# Motherboard.net
KiCad netlist of a schematic drawn in EAGLE
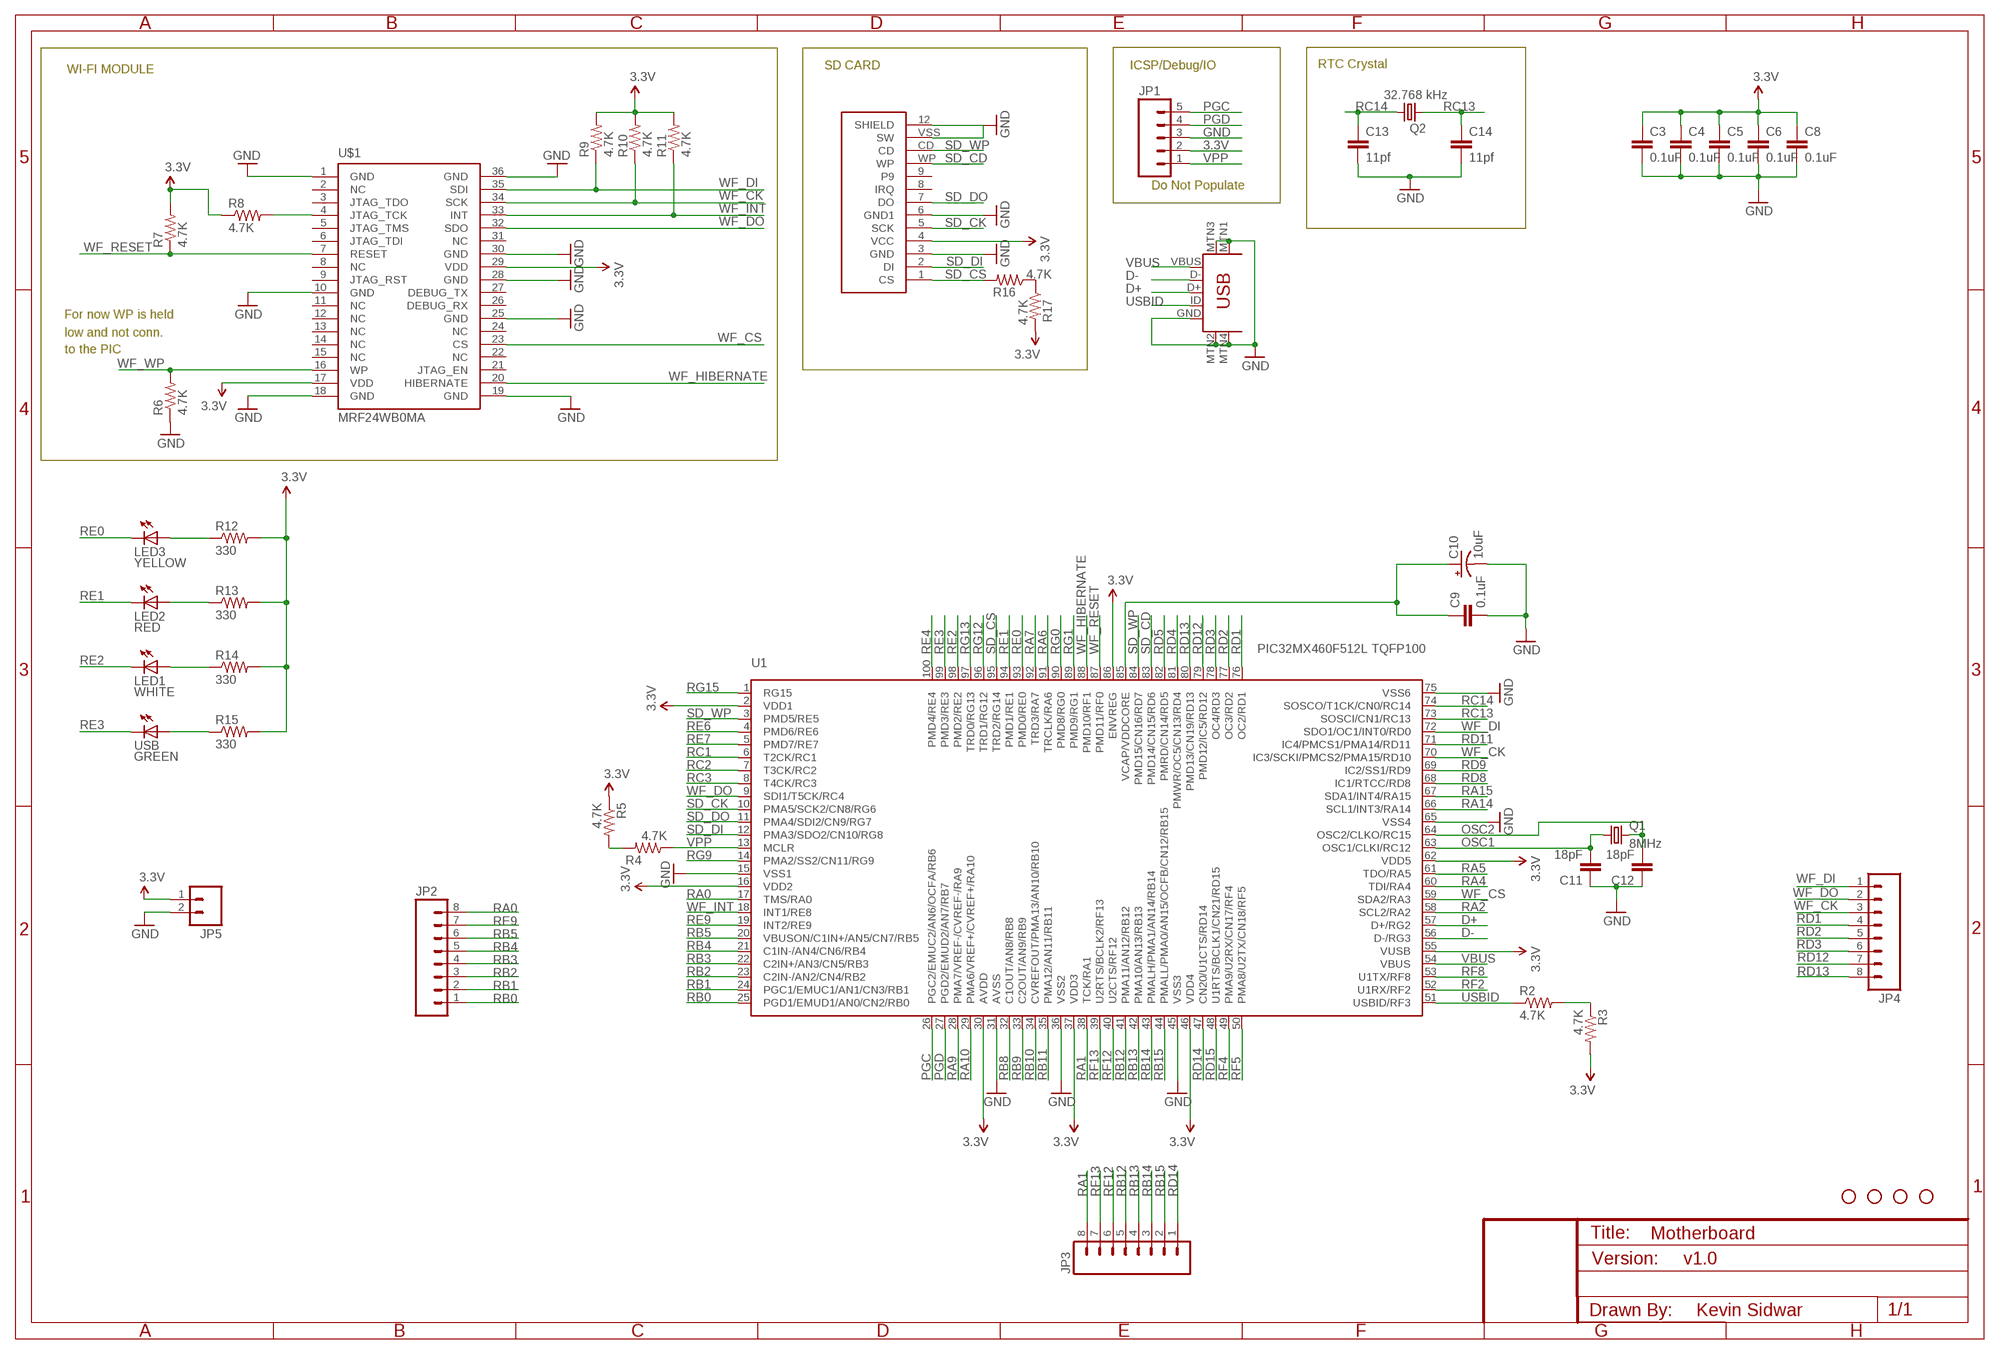
[diagram p0: schematic, sheet 1]

(export (version "E")
  (design (tool "Eeschema 10.0.6"))
  (components
    (comp (ref "C3")
      (value "0.1uF")
      (footprint "eagle-import:0603")
      (libsource (lib "eagle-import") (part "CAP0603"))
    )
    (comp (ref "C4")
      (value "0.1uF")
      (footprint "eagle-import:0603")
      (libsource (lib "eagle-import") (part "CAP0603"))
    )
    (comp (ref "C5")
      (value "0.1uF")
      (footprint "eagle-import:0603")
      (libsource (lib "eagle-import") (part "CAP0603"))
    )
    (comp (ref "C6")
      (value "0.1uF")
      (footprint "eagle-import:0603")
      (libsource (lib "eagle-import") (part "CAP0603"))
    )
    (comp (ref "C8")
      (value "0.1uF")
      (footprint "eagle-import:0603")
      (libsource (lib "eagle-import") (part "CAP0603"))
    )
    (comp (ref "C9")
      (value "0.1uF")
      (footprint "eagle-import:0603")
      (libsource (lib "eagle-import") (part "CAP0603"))
    )
    (comp (ref "C10")
      (value "10uF")
      (footprint "eagle-import:EIA3528")
      (libsource (lib "eagle-import") (part "CAP_POL3528"))
    )
    (comp (ref "C11")
      (value "18pF")
      (footprint "eagle-import:0603")
      (libsource (lib "eagle-import") (part "CAP0603"))
    )
    (comp (ref "C12")
      (value "18pF")
      (footprint "eagle-import:0603")
      (libsource (lib "eagle-import") (part "CAP0603"))
    )
    (comp (ref "C13")
      (value "11pf")
      (footprint "eagle-import:0603")
      (libsource (lib "eagle-import") (part "CAP0603"))
    )
    (comp (ref "C14")
      (value "11pf")
      (footprint "eagle-import:0603")
      (libsource (lib "eagle-import") (part "CAP0603"))
    )
    (comp (ref "JP1")
      (value "M05LOCK")
      (footprint "eagle-import:1X05_LOCK")
      (libsource (lib "eagle-import") (part "M05LOCK"))
    )
    (comp (ref "JP2")
      (value "M08LOCK")
      (footprint "eagle-import:1X08_LOCK")
      (libsource (lib "eagle-import") (part "M08LOCK"))
    )
    (comp (ref "JP3")
      (value "M08LOCK")
      (footprint "eagle-import:1X08_LOCK")
      (libsource (lib "eagle-import") (part "M08LOCK"))
    )
    (comp (ref "JP4")
      (value "M08LOCK")
      (footprint "eagle-import:1X08_LOCK")
      (libsource (lib "eagle-import") (part "M08LOCK"))
    )
    (comp (ref "JP5")
      (value "M02LOCK")
      (footprint "eagle-import:1X02_LOCK")
      (libsource (lib "eagle-import") (part "M02LOCK"))
    )
    (comp (ref "JP6")
      (value "STAND-OFF")
      (footprint "eagle-import:STAND-OFF")
      (libsource (lib "eagle-import") (part "STAND-OFF"))
    )
    (comp (ref "JP7")
      (value "STAND-OFF")
      (footprint "eagle-import:STAND-OFF")
      (libsource (lib "eagle-import") (part "STAND-OFF"))
    )
    (comp (ref "JP8")
      (value "STAND-OFF")
      (footprint "eagle-import:STAND-OFF")
      (libsource (lib "eagle-import") (part "STAND-OFF"))
    )
    (comp (ref "JP9")
      (value "STAND-OFF")
      (footprint "eagle-import:STAND-OFF")
      (libsource (lib "eagle-import") (part "STAND-OFF"))
    )
    (comp (ref "LED1")
      (value "WHITE")
      (footprint "eagle-import:LED-0603")
      (libsource (lib "eagle-import") (part "LED0603"))
    )
    (comp (ref "LED2")
      (value "RED")
      (footprint "eagle-import:LED-0603")
      (libsource (lib "eagle-import") (part "LED0603"))
    )
    (comp (ref "LED3")
      (value "YELLOW")
      (footprint "eagle-import:LED-0603")
      (libsource (lib "eagle-import") (part "LED0603"))
    )
    (comp (ref "Q1")
      (value "8MHz")
      (footprint "eagle-import:CRYSTAL-SMD-5X3")
      (libsource (lib "eagle-import") (part "CRYSTAL5X3"))
    )
    (comp (ref "Q2")
      (value "32.768 kHz")
      (footprint "eagle-import:CRYSTAL-SMD-4X2")
      (libsource (lib "eagle-import") (part "CRYSTAL"))
    )
    (comp (ref "R2")
      (value "4.7K")
      (footprint "eagle-import:0603-RES")
      (libsource (lib "eagle-import") (part "RESISTOR0603-RES"))
    )
    (comp (ref "R3")
      (value "4.7K")
      (footprint "eagle-import:0603-RES")
      (libsource (lib "eagle-import") (part "RESISTOR0603-RES"))
    )
    (comp (ref "R4")
      (value "4.7K")
      (footprint "eagle-import:0603-RES")
      (libsource (lib "eagle-import") (part "RESISTOR0603-RES"))
    )
    (comp (ref "R5")
      (value "4.7K")
      (footprint "eagle-import:0603-RES")
      (libsource (lib "eagle-import") (part "RESISTOR0603-RES"))
    )
    (comp (ref "R6")
      (value "4.7K")
      (footprint "eagle-import:0603-RES")
      (libsource (lib "eagle-import") (part "RESISTOR0603-RES"))
    )
    (comp (ref "R7")
      (value "4.7K")
      (footprint "eagle-import:0603-RES")
      (libsource (lib "eagle-import") (part "RESISTOR0603-RES"))
    )
    (comp (ref "R8")
      (value "4.7K")
      (footprint "eagle-import:0603-RES")
      (libsource (lib "eagle-import") (part "RESISTOR0603-RES"))
    )
    (comp (ref "R9")
      (value "4.7K")
      (footprint "eagle-import:0603-RES")
      (libsource (lib "eagle-import") (part "RESISTOR0603-RES"))
    )
    (comp (ref "R10")
      (value "4.7K")
      (footprint "eagle-import:0603-RES")
      (libsource (lib "eagle-import") (part "RESISTOR0603-RES"))
    )
    (comp (ref "R11")
      (value "4.7K")
      (footprint "eagle-import:0603-RES")
      (libsource (lib "eagle-import") (part "RESISTOR0603-RES"))
    )
    (comp (ref "R12")
      (value "330")
      (footprint "eagle-import:0603-RES")
      (libsource (lib "eagle-import") (part "RESISTOR0603-RES"))
    )
    (comp (ref "R13")
      (value "330")
      (footprint "eagle-import:0603-RES")
      (libsource (lib "eagle-import") (part "RESISTOR0603-RES"))
    )
    (comp (ref "R14")
      (value "330")
      (footprint "eagle-import:0603-RES")
      (libsource (lib "eagle-import") (part "RESISTOR0603-RES"))
    )
    (comp (ref "R15")
      (value "330")
      (footprint "eagle-import:0603-RES")
      (libsource (lib "eagle-import") (part "RESISTOR0603-RES"))
    )
    (comp (ref "R16")
      (value "4.7K")
      (footprint "eagle-import:0603-RES")
      (libsource (lib "eagle-import") (part "RESISTOR0603-RES"))
    )
    (comp (ref "R17")
      (value "4.7K")
      (footprint "eagle-import:0603-RES")
      (libsource (lib "eagle-import") (part "RESISTOR0603-RES"))
    )
    (comp (ref "U$1")
      (value "MRF24WB0MA")
      (footprint "eagle-import:SMD_MRF")
      (libsource (lib "eagle-import") (part "MRF24WB0MA"))
    )
    (comp (ref "U$2")
      (value "SD_CARD_SOCKETALPS")
      (footprint "eagle-import:SD_ALPS")
      (libsource (lib "eagle-import") (part "SD_CARD_SOCKETALPS"))
    )
    (comp (ref "U$21")
      (value "USB-MINIB-5PIN")
      (footprint "eagle-import:USB-MINIB")
      (libsource (lib "eagle-import") (part "USB-MINIB-5PIN"))
    )
    (comp (ref "U1")
      (value "PIC32MX460F512L TQFP100")
      (footprint "eagle-import:TQFP100")
      (libsource (lib "eagle-import") (part "PIC32MX4XXLTQFP100"))
    )
    (comp (ref "USB")
      (value "GREEN")
      (footprint "eagle-import:LED-0603")
      (libsource (lib "eagle-import") (part "LED0603"))
    )
  )
  (nets
    (net (code "1") (name "/D+") (class "Default")
      (node (ref "U$21") (pin "D+") (pinfunction "D+_D+") (pintype "bidirectional"))
      (node (ref "U1") (pin "57") (pinfunction "D+/RG2_57") (pintype "bidirectional"))
    )
    (net (code "2") (name "/D-") (class "Default")
      (node (ref "U$21") (pin "D-") (pinfunction "D-_D-") (pintype "bidirectional"))
      (node (ref "U1") (pin "56") (pinfunction "D-/RG3_56") (pintype "bidirectional"))
    )
    (net (code "3") (name "/OSC1") (class "Default")
      (node (ref "C11") (pin "2") (pinfunction "2_2") (pintype "passive"))
      (node (ref "Q1") (pin "1") (pinfunction "1_1") (pintype "passive"))
      (node (ref "U1") (pin "63") (pinfunction "OSC1/CLKI/RC12_63") (pintype "bidirectional"))
    )
    (net (code "4") (name "/OSC2") (class "Default")
      (node (ref "C12") (pin "2") (pinfunction "2_2") (pintype "passive"))
      (node (ref "Q1") (pin "3") (pinfunction "2_3") (pintype "passive"))
      (node (ref "U1") (pin "64") (pinfunction "OSC2/CLKO/RC15_64") (pintype "bidirectional"))
    )
    (net (code "5") (name "/PGC") (class "Default")
      (node (ref "JP1") (pin "5") (pinfunction "5_5") (pintype "passive"))
      (node (ref "U1") (pin "26") (pinfunction "PGC2/EMUC2/AN6/OCFA/RB6_26") (pintype "bidirectional"))
    )
    (net (code "6") (name "/PGD") (class "Default")
      (node (ref "JP1") (pin "4") (pinfunction "4_4") (pintype "passive"))
      (node (ref "U1") (pin "27") (pinfunction "PGD2/EMUD2/AN7/RB7_27") (pintype "bidirectional"))
    )
    (net (code "7") (name "/RA0") (class "Default")
      (node (ref "JP2") (pin "8") (pinfunction "8_8") (pintype "passive"))
      (node (ref "U1") (pin "17") (pinfunction "TMS/RA0_17") (pintype "bidirectional"))
    )
    (net (code "8") (name "/RA1") (class "Default")
      (node (ref "JP3") (pin "8") (pinfunction "8_8") (pintype "passive"))
      (node (ref "U1") (pin "38") (pinfunction "TCK/RA1_38") (pintype "bidirectional"))
    )
    (net (code "9") (name "/RA2") (class "Default")
      (node (ref "U1") (pin "58") (pinfunction "SCL2/RA2_58") (pintype "bidirectional"))
    )
    (net (code "10") (name "/RA4") (class "Default")
      (node (ref "U1") (pin "60") (pinfunction "TDI/RA4_60") (pintype "bidirectional"))
    )
    (net (code "11") (name "/RA5") (class "Default")
      (node (ref "U1") (pin "61") (pinfunction "TDO/RA5_61") (pintype "bidirectional"))
    )
    (net (code "12") (name "/RA6") (class "Default")
      (node (ref "U1") (pin "91") (pinfunction "TRCLK/RA6_91") (pintype "bidirectional"))
    )
    (net (code "13") (name "/RA7") (class "Default")
      (node (ref "U1") (pin "92") (pinfunction "TRD3/RA7_92") (pintype "bidirectional"))
    )
    (net (code "14") (name "/RA9") (class "Default")
      (node (ref "U1") (pin "28") (pinfunction "PMA7/VREF-/CVREF-/RA9_28") (pintype "bidirectional"))
    )
    (net (code "15") (name "/RA10") (class "Default")
      (node (ref "U1") (pin "29") (pinfunction "PMA6/VREF+/CVREF+/RA10_29") (pintype "bidirectional"))
    )
    (net (code "16") (name "/RA14") (class "Default")
      (node (ref "U1") (pin "66") (pinfunction "SCL1/INT3/RA14_66") (pintype "bidirectional"))
    )
    (net (code "17") (name "/RA15") (class "Default")
      (node (ref "U1") (pin "67") (pinfunction "SDA1/INT4/RA15_67") (pintype "bidirectional"))
    )
    (net (code "18") (name "/RB0") (class "Default")
      (node (ref "JP2") (pin "1") (pinfunction "1_1") (pintype "passive"))
      (node (ref "U1") (pin "25") (pinfunction "PGD1/EMUD1/AN0/CN2/RB0_25") (pintype "bidirectional"))
    )
    (net (code "19") (name "/RB1") (class "Default")
      (node (ref "JP2") (pin "2") (pinfunction "2_2") (pintype "passive"))
      (node (ref "U1") (pin "24") (pinfunction "PGC1/EMUC1/AN1/CN3/RB1_24") (pintype "bidirectional"))
    )
    (net (code "20") (name "/RB2") (class "Default")
      (node (ref "JP2") (pin "3") (pinfunction "3_3") (pintype "passive"))
      (node (ref "U1") (pin "23") (pinfunction "C2IN-/AN2/CN4/RB2_23") (pintype "bidirectional"))
    )
    (net (code "21") (name "/RB3") (class "Default")
      (node (ref "JP2") (pin "4") (pinfunction "4_4") (pintype "passive"))
      (node (ref "U1") (pin "22") (pinfunction "C2IN+/AN3/CN5/RB3_22") (pintype "bidirectional"))
    )
    (net (code "22") (name "/RB4") (class "Default")
      (node (ref "JP2") (pin "5") (pinfunction "5_5") (pintype "passive"))
      (node (ref "U1") (pin "21") (pinfunction "C1IN-/AN4/CN6/RB4_21") (pintype "bidirectional"))
    )
    (net (code "23") (name "/RB5") (class "Default")
      (node (ref "JP2") (pin "6") (pinfunction "6_6") (pintype "passive"))
      (node (ref "U1") (pin "20") (pinfunction "VBUSON/C1IN+/AN5/CN7/RB5_20") (pintype "bidirectional"))
    )
    (net (code "24") (name "/RB8") (class "Default")
      (node (ref "U1") (pin "32") (pinfunction "C1OUT/AN8/RB8_32") (pintype "bidirectional"))
    )
    (net (code "25") (name "/RB9") (class "Default")
      (node (ref "U1") (pin "33") (pinfunction "C2OUT/AN9/RB9_33") (pintype "bidirectional"))
    )
    (net (code "26") (name "/RB10") (class "Default")
      (node (ref "U1") (pin "34") (pinfunction "CVREFOUT/PMA13/AN10/RB10_34") (pintype "bidirectional"))
    )
    (net (code "27") (name "/RB11") (class "Default")
      (node (ref "U1") (pin "35") (pinfunction "PMA12/AN11/RB11_35") (pintype "bidirectional"))
    )
    (net (code "28") (name "/RB12") (class "Default")
      (node (ref "JP3") (pin "5") (pinfunction "5_5") (pintype "passive"))
      (node (ref "U1") (pin "41") (pinfunction "PMA11/AN12/RB12_41") (pintype "bidirectional"))
    )
    (net (code "29") (name "/RB13") (class "Default")
      (node (ref "JP3") (pin "4") (pinfunction "4_4") (pintype "passive"))
      (node (ref "U1") (pin "42") (pinfunction "PMA10/AN13/RB13_42") (pintype "bidirectional"))
    )
    (net (code "30") (name "/RB14") (class "Default")
      (node (ref "JP3") (pin "3") (pinfunction "3_3") (pintype "passive"))
      (node (ref "U1") (pin "43") (pinfunction "PMALH/PMA1/AN14/RB14_43") (pintype "bidirectional"))
    )
    (net (code "31") (name "/RB15") (class "Default")
      (node (ref "JP3") (pin "2") (pinfunction "2_2") (pintype "passive"))
      (node (ref "U1") (pin "44") (pinfunction "PMALL/PMA0/AN15/OCFB/CN12/RB15_44") (pintype "bidirectional"))
    )
    (net (code "32") (name "/RC1") (class "Default")
      (node (ref "U1") (pin "6") (pinfunction "T2CK/RC1_6") (pintype "bidirectional"))
    )
    (net (code "33") (name "/RC2") (class "Default")
      (node (ref "U1") (pin "7") (pinfunction "T3CK/RC2_7") (pintype "bidirectional"))
    )
    (net (code "34") (name "/RC3") (class "Default")
      (node (ref "U1") (pin "8") (pinfunction "T4CK/RC3_8") (pintype "bidirectional"))
    )
    (net (code "35") (name "/RC13") (class "Default")
      (node (ref "C14") (pin "1") (pinfunction "1_1") (pintype "passive"))
      (node (ref "Q2") (pin "P$2") (pinfunction "2_P$2") (pintype "passive"))
      (node (ref "U1") (pin "73") (pinfunction "SOSCI/CN1/RC13_73") (pintype "bidirectional"))
    )
    (net (code "36") (name "/RC14") (class "Default")
      (node (ref "C13") (pin "1") (pinfunction "1_1") (pintype "passive"))
      (node (ref "Q2") (pin "P$1") (pinfunction "1_P$1") (pintype "passive"))
      (node (ref "U1") (pin "74") (pinfunction "SOSCO/T1CK/CN0/RC14_74") (pintype "bidirectional"))
    )
    (net (code "37") (name "/RD1") (class "Default")
      (node (ref "JP4") (pin "4") (pinfunction "4_4") (pintype "passive"))
      (node (ref "U1") (pin "76") (pinfunction "OC2/RD1_76") (pintype "bidirectional"))
    )
    (net (code "38") (name "/RD2") (class "Default")
      (node (ref "JP4") (pin "5") (pinfunction "5_5") (pintype "passive"))
      (node (ref "U1") (pin "77") (pinfunction "OC3/RD2_77") (pintype "bidirectional"))
    )
    (net (code "39") (name "/RD3") (class "Default")
      (node (ref "JP4") (pin "6") (pinfunction "6_6") (pintype "passive"))
      (node (ref "U1") (pin "78") (pinfunction "OC4/RD3_78") (pintype "bidirectional"))
    )
    (net (code "40") (name "/RD4") (class "Default")
      (node (ref "U1") (pin "81") (pinfunction "PMWR/OC5/CN13/RD4_81") (pintype "bidirectional"))
    )
    (net (code "41") (name "/RD5") (class "Default")
      (node (ref "U1") (pin "82") (pinfunction "PMRD/CN14/RD5_82") (pintype "bidirectional"))
    )
    (net (code "42") (name "/RD8") (class "Default")
      (node (ref "U1") (pin "68") (pinfunction "IC1/RTCC/RD8_68") (pintype "bidirectional"))
    )
    (net (code "43") (name "/RD9") (class "Default")
      (node (ref "U1") (pin "69") (pinfunction "IC2/SS1/RD9_69") (pintype "bidirectional"))
    )
    (net (code "44") (name "/RD11") (class "Default")
      (node (ref "U1") (pin "71") (pinfunction "IC4/PMCS1/PMA14/RD11_71") (pintype "bidirectional"))
    )
    (net (code "45") (name "/RD12") (class "Default")
      (node (ref "JP4") (pin "7") (pinfunction "7_7") (pintype "passive"))
      (node (ref "U1") (pin "79") (pinfunction "PMD12/IC5/RD12_79") (pintype "bidirectional"))
    )
    (net (code "46") (name "/RD13") (class "Default")
      (node (ref "JP4") (pin "8") (pinfunction "8_8") (pintype "passive"))
      (node (ref "U1") (pin "80") (pinfunction "PMD13/CN19/RD13_80") (pintype "bidirectional"))
    )
    (net (code "47") (name "/RD14") (class "Default")
      (node (ref "JP3") (pin "1") (pinfunction "1_1") (pintype "passive"))
      (node (ref "U1") (pin "47") (pinfunction "CN20/U1CTS/RD14_47") (pintype "bidirectional"))
    )
    (net (code "48") (name "/RD15") (class "Default")
      (node (ref "U1") (pin "48") (pinfunction "U1RTS/BCLK1/CN21/RD15_48") (pintype "bidirectional"))
    )
    (net (code "49") (name "/RE0") (class "Default")
      (node (ref "LED3") (pin "C") (pinfunction "C_C") (pintype "passive"))
      (node (ref "U1") (pin "93") (pinfunction "PMD0/RE0_93") (pintype "bidirectional"))
    )
    (net (code "50") (name "/RE1") (class "Default")
      (node (ref "LED2") (pin "C") (pinfunction "C_C") (pintype "passive"))
      (node (ref "U1") (pin "94") (pinfunction "PMD1/RE1_94") (pintype "bidirectional"))
    )
    (net (code "51") (name "/RE2") (class "Default")
      (node (ref "LED1") (pin "C") (pinfunction "C_C") (pintype "passive"))
      (node (ref "U1") (pin "98") (pinfunction "PMD2/RE2_98") (pintype "bidirectional"))
    )
    (net (code "52") (name "/RE3") (class "Default")
      (node (ref "U1") (pin "99") (pinfunction "PMD3/RE3_99") (pintype "bidirectional"))
      (node (ref "USB") (pin "C") (pinfunction "C_C") (pintype "passive"))
    )
    (net (code "53") (name "/RE4") (class "Default")
      (node (ref "U1") (pin "100") (pinfunction "PMD4/RE4_100") (pintype "bidirectional"))
    )
    (net (code "54") (name "/RE6") (class "Default")
      (node (ref "U1") (pin "4") (pinfunction "PMD6/RE6_4") (pintype "bidirectional"))
    )
    (net (code "55") (name "/RE7") (class "Default")
      (node (ref "U1") (pin "5") (pinfunction "PMD7/RE7_5") (pintype "bidirectional"))
    )
    (net (code "56") (name "/RE9") (class "Default")
      (node (ref "JP2") (pin "7") (pinfunction "7_7") (pintype "passive"))
      (node (ref "U1") (pin "19") (pinfunction "INT2/RE9_19") (pintype "bidirectional"))
    )
    (net (code "57") (name "/RF2") (class "Default")
      (node (ref "U1") (pin "52") (pinfunction "U1RX/RF2_52") (pintype "bidirectional"))
    )
    (net (code "58") (name "/RF4") (class "Default")
      (node (ref "U1") (pin "49") (pinfunction "PMA9/U2RX/CN17/RF4_49") (pintype "bidirectional"))
    )
    (net (code "59") (name "/RF5") (class "Default")
      (node (ref "U1") (pin "50") (pinfunction "PMA8/U2TX/CN18/RF5_50") (pintype "bidirectional"))
    )
    (net (code "60") (name "/RF8") (class "Default")
      (node (ref "U1") (pin "53") (pinfunction "U1TX/RF8_53") (pintype "bidirectional"))
    )
    (net (code "61") (name "/RF12") (class "Default")
      (node (ref "JP3") (pin "6") (pinfunction "6_6") (pintype "passive"))
      (node (ref "U1") (pin "40") (pinfunction "U2CTS/RF12_40") (pintype "bidirectional"))
    )
    (net (code "62") (name "/RF13") (class "Default")
      (node (ref "JP3") (pin "7") (pinfunction "7_7") (pintype "passive"))
      (node (ref "U1") (pin "39") (pinfunction "U2RTS/BCLK2/RF13_39") (pintype "bidirectional"))
    )
    (net (code "63") (name "/RG0") (class "Default")
      (node (ref "U1") (pin "90") (pinfunction "PMD8/RG0_90") (pintype "bidirectional"))
    )
    (net (code "64") (name "/RG1") (class "Default")
      (node (ref "U1") (pin "89") (pinfunction "PMD9/RG1_89") (pintype "bidirectional"))
    )
    (net (code "65") (name "/RG9") (class "Default")
      (node (ref "U1") (pin "14") (pinfunction "PMA2/SS2/CN11/RG9_14") (pintype "bidirectional"))
    )
    (net (code "66") (name "/RG12") (class "Default")
      (node (ref "U1") (pin "96") (pinfunction "TRD1/RG12_96") (pintype "bidirectional"))
    )
    (net (code "67") (name "/RG13") (class "Default")
      (node (ref "U1") (pin "97") (pinfunction "TRD0/RG13_97") (pintype "bidirectional"))
    )
    (net (code "68") (name "/RG15") (class "Default")
      (node (ref "U1") (pin "1") (pinfunction "RG15_1") (pintype "bidirectional"))
    )
    (net (code "69") (name "/SD_CD") (class "Default")
      (node (ref "U$2") (pin "WP") (pinfunction "WP_WP") (pintype "bidirectional"))
      (node (ref "U1") (pin "83") (pinfunction "PMD14/CN15/RD6_83") (pintype "bidirectional"))
    )
    (net (code "70") (name "/SD_CK") (class "Default")
      (node (ref "U$2") (pin "5") (pinfunction "SCK_5") (pintype "bidirectional"))
      (node (ref "U1") (pin "10") (pinfunction "PMA5/SCK2/CN8/RG6_10") (pintype "bidirectional"))
    )
    (net (code "71") (name "/SD_CS") (class "Default")
      (node (ref "R16") (pin "2") (pinfunction "2_2") (pintype "passive"))
      (node (ref "U$2") (pin "1") (pinfunction "CS_1") (pintype "bidirectional"))
      (node (ref "U1") (pin "95") (pinfunction "TRD2/RG14_95") (pintype "bidirectional"))
    )
    (net (code "72") (name "/SD_DI") (class "Default")
      (node (ref "U$2") (pin "2") (pinfunction "DI_2") (pintype "bidirectional"))
      (node (ref "U1") (pin "12") (pinfunction "PMA3/SDO2/CN10/RG8_12") (pintype "bidirectional"))
    )
    (net (code "73") (name "/SD_DO") (class "Default")
      (node (ref "U$2") (pin "7") (pinfunction "DO_7") (pintype "bidirectional"))
      (node (ref "U1") (pin "11") (pinfunction "PMA4/SDI2/CN9/RG7_11") (pintype "bidirectional"))
    )
    (net (code "74") (name "/SD_WP") (class "Default")
      (node (ref "U$2") (pin "CD") (pinfunction "CD_CD") (pintype "bidirectional"))
      (node (ref "U1") (pin "3") (pinfunction "PMD5/RE5_3") (pintype "bidirectional"))
      (node (ref "U1") (pin "84") (pinfunction "PMD15/CN16/RD7_84") (pintype "bidirectional"))
    )
    (net (code "75") (name "/USBID") (class "Default")
      (node (ref "R2") (pin "1") (pinfunction "1_1") (pintype "passive"))
      (node (ref "U$21") (pin "ID") (pinfunction "ID_ID") (pintype "bidirectional"))
      (node (ref "U1") (pin "51") (pinfunction "USBID/RF3_51") (pintype "bidirectional"))
    )
    (net (code "76") (name "/VBUS") (class "Default")
      (node (ref "U$21") (pin "VBUS") (pinfunction "VBUS_VBUS") (pintype "bidirectional"))
      (node (ref "U1") (pin "54") (pinfunction "VBUS_54") (pintype "bidirectional"))
    )
    (net (code "77") (name "/VPP") (class "Default")
      (node (ref "JP1") (pin "1") (pinfunction "1_1") (pintype "passive"))
      (node (ref "R4") (pin "1") (pinfunction "1_1") (pintype "passive"))
      (node (ref "U1") (pin "13") (pinfunction "MCLR_13") (pintype "bidirectional"))
    )
    (net (code "78") (name "/WF_CK") (class "Default")
      (node (ref "JP4") (pin "3") (pinfunction "3_3") (pintype "passive"))
      (node (ref "R10") (pin "1") (pinfunction "1_1") (pintype "passive"))
      (node (ref "U$1") (pin "34") (pinfunction "SCK_34") (pintype "bidirectional"))
      (node (ref "U1") (pin "70") (pinfunction "IC3/SCKI/PMCS2/PMA15/RD10_70") (pintype "bidirectional"))
    )
    (net (code "79") (name "/WF_CS") (class "Default")
      (node (ref "U$1") (pin "23") (pinfunction "CS_23") (pintype "bidirectional"))
      (node (ref "U1") (pin "59") (pinfunction "SDA2/RA3_59") (pintype "bidirectional"))
    )
    (net (code "80") (name "/WF_DI") (class "Default")
      (node (ref "JP4") (pin "1") (pinfunction "1_1") (pintype "passive"))
      (node (ref "R9") (pin "1") (pinfunction "1_1") (pintype "passive"))
      (node (ref "U$1") (pin "35") (pinfunction "SDI_35") (pintype "bidirectional"))
      (node (ref "U1") (pin "72") (pinfunction "SDO1/OC1/INT0/RD0_72") (pintype "bidirectional"))
    )
    (net (code "81") (name "/WF_DO") (class "Default")
      (node (ref "JP4") (pin "2") (pinfunction "2_2") (pintype "passive"))
      (node (ref "U$1") (pin "32") (pinfunction "SDO_32") (pintype "bidirectional"))
      (node (ref "U1") (pin "9") (pinfunction "SDI1/T5CK/RC4_9") (pintype "bidirectional"))
    )
    (net (code "82") (name "/WF_HIBERNATE") (class "Default")
      (node (ref "U$1") (pin "20") (pinfunction "HIBERNATE_20") (pintype "bidirectional"))
      (node (ref "U1") (pin "88") (pinfunction "PMD10/RF1_88") (pintype "bidirectional"))
    )
    (net (code "83") (name "/WF_INT") (class "Default")
      (node (ref "R11") (pin "1") (pinfunction "1_1") (pintype "passive"))
      (node (ref "U$1") (pin "33") (pinfunction "INT_33") (pintype "bidirectional"))
      (node (ref "U1") (pin "18") (pinfunction "INT1/RE8_18") (pintype "bidirectional"))
    )
    (net (code "84") (name "/WF_RESET") (class "Default")
      (node (ref "R7") (pin "1") (pinfunction "1_1") (pintype "passive"))
      (node (ref "U$1") (pin "7") (pinfunction "RESET_7") (pintype "bidirectional"))
      (node (ref "U1") (pin "87") (pinfunction "PMD11/RF0_87") (pintype "bidirectional"))
    )
    (net (code "85") (name "/WF_WP") (class "Default")
      (node (ref "R6") (pin "2") (pinfunction "2_2") (pintype "passive"))
      (node (ref "U$1") (pin "16") (pinfunction "WP_16") (pintype "bidirectional"))
    )
    (net (code "86") (name "3.3V") (class "Default")
      (node (ref "C3") (pin "1") (pinfunction "1_1") (pintype "passive"))
      (node (ref "C4") (pin "1") (pinfunction "1_1") (pintype "passive"))
      (node (ref "C5") (pin "1") (pinfunction "1_1") (pintype "passive"))
      (node (ref "C6") (pin "1") (pinfunction "1_1") (pintype "passive"))
      (node (ref "C8") (pin "1") (pinfunction "1_1") (pintype "passive"))
      (node (ref "JP1") (pin "2") (pinfunction "2_2") (pintype "passive"))
      (node (ref "JP5") (pin "1") (pinfunction "1_1") (pintype "passive"))
      (node (ref "R10") (pin "2") (pinfunction "2_2") (pintype "passive"))
      (node (ref "R11") (pin "2") (pinfunction "2_2") (pintype "passive"))
      (node (ref "R12") (pin "2") (pinfunction "2_2") (pintype "passive"))
      (node (ref "R13") (pin "2") (pinfunction "2_2") (pintype "passive"))
      (node (ref "R14") (pin "2") (pinfunction "2_2") (pintype "passive"))
      (node (ref "R15") (pin "2") (pinfunction "2_2") (pintype "passive"))
      (node (ref "R17") (pin "2") (pinfunction "2_2") (pintype "passive"))
      (node (ref "R3") (pin "2") (pinfunction "2_2") (pintype "passive"))
      (node (ref "R5") (pin "1") (pinfunction "1_1") (pintype "passive"))
      (node (ref "R7") (pin "2") (pinfunction "2_2") (pintype "passive"))
      (node (ref "R8") (pin "1") (pinfunction "1_1") (pintype "passive"))
      (node (ref "R9") (pin "2") (pinfunction "2_2") (pintype "passive"))
      (node (ref "U$1") (pin "17") (pinfunction "VDD_17") (pintype "bidirectional"))
      (node (ref "U$1") (pin "29") (pinfunction "VDD_29") (pintype "bidirectional"))
      (node (ref "U$2") (pin "4") (pinfunction "VCC_4") (pintype "bidirectional"))
      (node (ref "U1") (pin "16") (pinfunction "VDD2_16") (pintype "bidirectional"))
      (node (ref "U1") (pin "2") (pinfunction "VDD1_2") (pintype "bidirectional"))
      (node (ref "U1") (pin "30") (pinfunction "AVDD_30") (pintype "bidirectional"))
      (node (ref "U1") (pin "37") (pinfunction "VDD3_37") (pintype "bidirectional"))
      (node (ref "U1") (pin "46") (pinfunction "VDD4_46") (pintype "bidirectional"))
      (node (ref "U1") (pin "55") (pinfunction "VUSB_55") (pintype "bidirectional"))
      (node (ref "U1") (pin "62") (pinfunction "VDD5_62") (pintype "bidirectional"))
      (node (ref "U1") (pin "86") (pinfunction "ENVREG_86") (pintype "bidirectional"))
    )
    (net (code "87") (name "GND") (class "Default")
      (node (ref "C10") (pin "C") (pinfunction "-_C") (pintype "passive"))
      (node (ref "C11") (pin "1") (pinfunction "1_1") (pintype "passive"))
      (node (ref "C12") (pin "1") (pinfunction "1_1") (pintype "passive"))
      (node (ref "C13") (pin "2") (pinfunction "2_2") (pintype "passive"))
      (node (ref "C14") (pin "2") (pinfunction "2_2") (pintype "passive"))
      (node (ref "C3") (pin "2") (pinfunction "2_2") (pintype "passive"))
      (node (ref "C4") (pin "2") (pinfunction "2_2") (pintype "passive"))
      (node (ref "C5") (pin "2") (pinfunction "2_2") (pintype "passive"))
      (node (ref "C6") (pin "2") (pinfunction "2_2") (pintype "passive"))
      (node (ref "C8") (pin "2") (pinfunction "2_2") (pintype "passive"))
      (node (ref "C9") (pin "2") (pinfunction "2_2") (pintype "passive"))
      (node (ref "JP1") (pin "3") (pinfunction "3_3") (pintype "passive"))
      (node (ref "JP5") (pin "2") (pinfunction "2_2") (pintype "passive"))
      (node (ref "R6") (pin "1") (pinfunction "1_1") (pintype "passive"))
      (node (ref "U$1") (pin "1") (pinfunction "GND_1") (pintype "bidirectional"))
      (node (ref "U$1") (pin "10") (pinfunction "GND_10") (pintype "bidirectional"))
      (node (ref "U$1") (pin "18") (pinfunction "GND_18") (pintype "bidirectional"))
      (node (ref "U$1") (pin "19") (pinfunction "GND_19") (pintype "bidirectional"))
      (node (ref "U$1") (pin "25") (pinfunction "GND_25") (pintype "bidirectional"))
      (node (ref "U$1") (pin "28") (pinfunction "GND_28") (pintype "bidirectional"))
      (node (ref "U$1") (pin "30") (pinfunction "GND_30") (pintype "bidirectional"))
      (node (ref "U$1") (pin "36") (pinfunction "GND_36") (pintype "bidirectional"))
      (node (ref "U$2") (pin "12") (pinfunction "SHIELD_12") (pintype "bidirectional"))
      (node (ref "U$2") (pin "3") (pinfunction "GND_3") (pintype "bidirectional"))
      (node (ref "U$2") (pin "6") (pinfunction "GND1_6") (pintype "bidirectional"))
      (node (ref "U$2") (pin "VSS") (pinfunction "SW_VSS") (pintype "bidirectional"))
      (node (ref "U$21") (pin "GND") (pinfunction "GND_GND") (pintype "bidirectional"))
      (node (ref "U$21") (pin "MTN1") (pinfunction "MTN2_MTN1") (pintype "bidirectional"))
      (node (ref "U$21") (pin "MTN2") (pinfunction "MTN3_MTN2") (pintype "bidirectional"))
      (node (ref "U$21") (pin "MTN3") (pinfunction "MTN1_MTN3") (pintype "bidirectional"))
      (node (ref "U$21") (pin "MTN4") (pinfunction "MTN4_MTN4") (pintype "bidirectional"))
      (node (ref "U1") (pin "15") (pinfunction "VSS1_15") (pintype "bidirectional"))
      (node (ref "U1") (pin "31") (pinfunction "AVSS_31") (pintype "bidirectional"))
      (node (ref "U1") (pin "36") (pinfunction "VSS2_36") (pintype "bidirectional"))
      (node (ref "U1") (pin "45") (pinfunction "VSS3_45") (pintype "bidirectional"))
      (node (ref "U1") (pin "65") (pinfunction "VSS4_65") (pintype "bidirectional"))
      (node (ref "U1") (pin "75") (pinfunction "VSS6_75") (pintype "bidirectional"))
    )
    (net (code "88") (name "Net-(C10-+)") (class "Default")
      (node (ref "C10") (pin "A") (pinfunction "+_A") (pintype "passive"))
      (node (ref "C9") (pin "1") (pinfunction "1_1") (pintype "passive"))
      (node (ref "U1") (pin "85") (pinfunction "VCAP/VDDCORE_85") (pintype "bidirectional"))
    )
    (net (code "89") (name "Net-(LED1-PadA)") (class "Default")
      (node (ref "LED1") (pin "A") (pinfunction "A_A") (pintype "passive"))
      (node (ref "R14") (pin "1") (pinfunction "1_1") (pintype "passive"))
    )
    (net (code "90") (name "Net-(LED2-PadA)") (class "Default")
      (node (ref "LED2") (pin "A") (pinfunction "A_A") (pintype "passive"))
      (node (ref "R13") (pin "1") (pinfunction "1_1") (pintype "passive"))
    )
    (net (code "91") (name "Net-(LED3-PadA)") (class "Default")
      (node (ref "LED3") (pin "A") (pinfunction "A_A") (pintype "passive"))
      (node (ref "R12") (pin "1") (pinfunction "1_1") (pintype "passive"))
    )
    (net (code "92") (name "Net-(R2-Pad2)") (class "Default")
      (node (ref "R2") (pin "2") (pinfunction "2_2") (pintype "passive"))
      (node (ref "R3") (pin "1") (pinfunction "1_1") (pintype "passive"))
    )
    (net (code "93") (name "Net-(R4-Pad2)") (class "Default")
      (node (ref "R4") (pin "2") (pinfunction "2_2") (pintype "passive"))
      (node (ref "R5") (pin "2") (pinfunction "2_2") (pintype "passive"))
    )
    (net (code "94") (name "Net-(R15-Pad1)") (class "Default")
      (node (ref "R15") (pin "1") (pinfunction "1_1") (pintype "passive"))
      (node (ref "USB") (pin "A") (pinfunction "A_A") (pintype "passive"))
    )
    (net (code "95") (name "Net-(R16-Pad1)") (class "Default")
      (node (ref "R16") (pin "1") (pinfunction "1_1") (pintype "passive"))
      (node (ref "R17") (pin "1") (pinfunction "1_1") (pintype "passive"))
    )
    (net (code "96") (name "Net-(U$1-JTAG_TCK)") (class "Default")
      (node (ref "R8") (pin "2") (pinfunction "2_2") (pintype "passive"))
      (node (ref "U$1") (pin "4") (pinfunction "JTAG_TCK_4") (pintype "bidirectional"))
    )
    (net (code "97") (name "unconnected-(U$1-DEBUG_RX-Pad26)") (class "Default")
      (node (ref "U$1") (pin "26") (pinfunction "DEBUG_RX_26") (pintype "bidirectional"))
    )
    (net (code "98") (name "unconnected-(U$1-DEBUG_TX-Pad27)") (class "Default")
      (node (ref "U$1") (pin "27") (pinfunction "DEBUG_TX_27") (pintype "bidirectional"))
    )
    (net (code "99") (name "unconnected-(U$1-JTAG_EN-Pad21)") (class "Default")
      (node (ref "U$1") (pin "21") (pinfunction "JTAG_EN_21") (pintype "bidirectional"))
    )
    (net (code "100") (name "unconnected-(U$1-JTAG_RST-Pad9)") (class "Default")
      (node (ref "U$1") (pin "9") (pinfunction "JTAG_RST_9") (pintype "bidirectional"))
    )
    (net (code "101") (name "unconnected-(U$1-JTAG_TDI-Pad6)") (class "Default")
      (node (ref "U$1") (pin "6") (pinfunction "JTAG_TDI_6") (pintype "bidirectional"))
    )
    (net (code "102") (name "unconnected-(U$1-JTAG_TDO-Pad3)") (class "Default")
      (node (ref "U$1") (pin "3") (pinfunction "JTAG_TDO_3") (pintype "bidirectional"))
    )
    (net (code "103") (name "unconnected-(U$1-JTAG_TMS-Pad5)") (class "Default")
      (node (ref "U$1") (pin "5") (pinfunction "JTAG_TMS_5") (pintype "bidirectional"))
    )
    (net (code "104") (name "unconnected-(U$1-NC-Pad2)") (class "Default")
      (node (ref "U$1") (pin "2") (pinfunction "NC_2") (pintype "bidirectional"))
    )
    (net (code "105") (name "unconnected-(U$1-NC-Pad8)") (class "Default")
      (node (ref "U$1") (pin "8") (pinfunction "NC_8") (pintype "bidirectional"))
    )
    (net (code "106") (name "unconnected-(U$1-NC-Pad11)") (class "Default")
      (node (ref "U$1") (pin "11") (pinfunction "NC_11") (pintype "bidirectional"))
    )
    (net (code "107") (name "unconnected-(U$1-NC-Pad12)") (class "Default")
      (node (ref "U$1") (pin "12") (pinfunction "NC_12") (pintype "bidirectional"))
    )
    (net (code "108") (name "unconnected-(U$1-NC-Pad13)") (class "Default")
      (node (ref "U$1") (pin "13") (pinfunction "NC_13") (pintype "bidirectional"))
    )
    (net (code "109") (name "unconnected-(U$1-NC-Pad14)") (class "Default")
      (node (ref "U$1") (pin "14") (pinfunction "NC_14") (pintype "bidirectional"))
    )
    (net (code "110") (name "unconnected-(U$1-NC-Pad15)") (class "Default")
      (node (ref "U$1") (pin "15") (pinfunction "NC_15") (pintype "bidirectional"))
    )
    (net (code "111") (name "unconnected-(U$1-NC-Pad22)") (class "Default")
      (node (ref "U$1") (pin "22") (pinfunction "NC_22") (pintype "bidirectional"))
    )
    (net (code "112") (name "unconnected-(U$1-NC-Pad24)") (class "Default")
      (node (ref "U$1") (pin "24") (pinfunction "NC_24") (pintype "bidirectional"))
    )
    (net (code "113") (name "unconnected-(U$1-NC-Pad31)") (class "Default")
      (node (ref "U$1") (pin "31") (pinfunction "NC_31") (pintype "bidirectional"))
    )
    (net (code "114") (name "unconnected-(U$2-IRQ-Pad8)") (class "Default")
      (node (ref "U$2") (pin "8") (pinfunction "IRQ_8") (pintype "bidirectional"))
    )
    (net (code "115") (name "unconnected-(U$2-P9-Pad9)") (class "Default")
      (node (ref "U$2") (pin "9") (pinfunction "P9_9") (pintype "bidirectional"))
    )
  )
)
